# Jonah.net
KiCad netlist of a schematic drawn in EAGLE
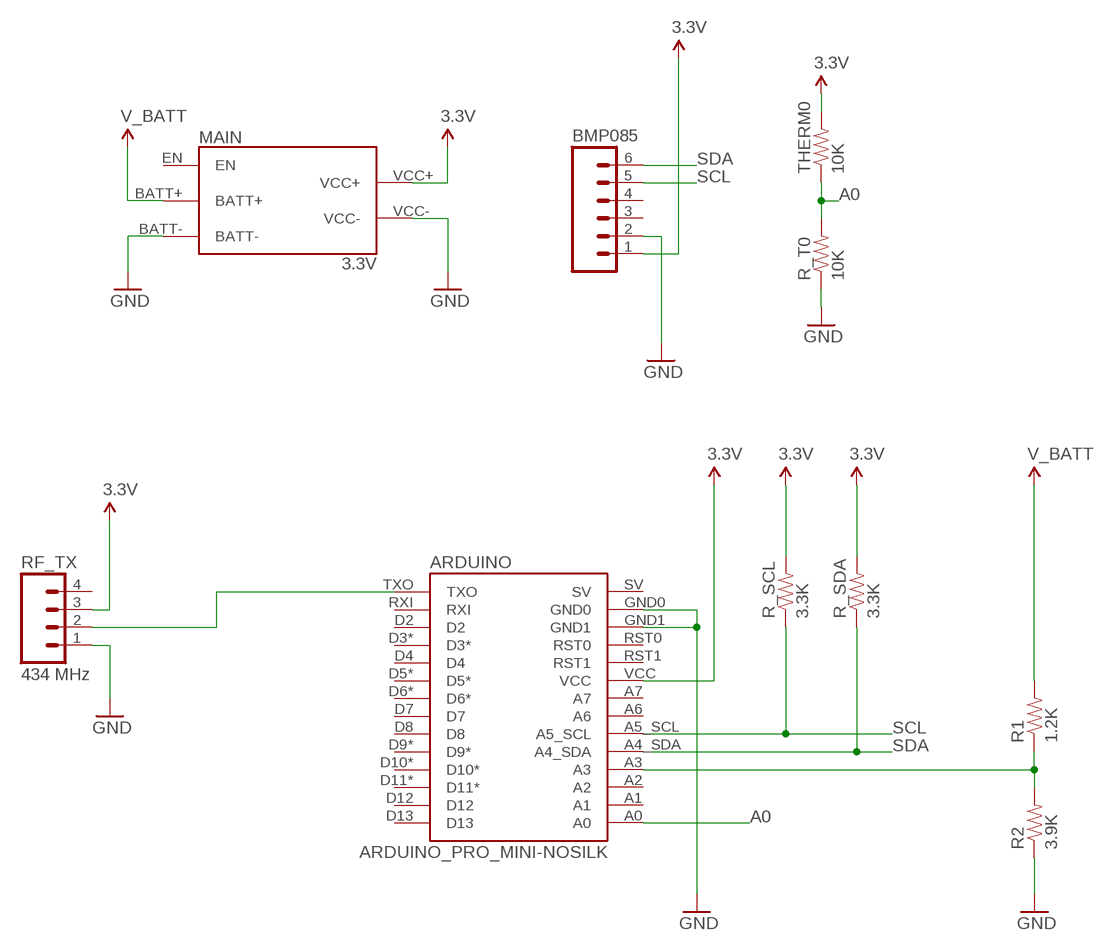
[diagram p0: schematic, sheet 1]

(export (version "E")
  (design (tool "Eeschema 10.0.6"))
  (components
    (comp (ref "ARDUINO")
      (value "ARDUINO_PRO_MINI-NOSILK")
      (footprint "eagle-import:ARDUINO_PRO_MINI-NOSILK")
      (libsource (lib "eagle-import") (part "ARDUINO_PRO_MINI-NOSILK"))
    )
    (comp (ref "BMP085")
      (value "M06SIP")
      (footprint "eagle-import:1X06")
      (libsource (lib "eagle-import") (part "M06SIP"))
    )
    (comp (ref "MAIN")
      (value "3.3V")
      (footprint "eagle-import:POWER-TPS6300X-NOSILK")
      (libsource (lib "eagle-import") (part "POWER-TPS6300X-NOSILK"))
    )
    (comp (ref "R1")
      (value "1.2K")
      (footprint "eagle-import:0805")
      (libsource (lib "eagle-import") (part "RESISTOR0805-RES"))
    )
    (comp (ref "R2")
      (value "3.9K")
      (footprint "eagle-import:0805")
      (libsource (lib "eagle-import") (part "RESISTOR0805-RES"))
    )
    (comp (ref "RF_TX")
      (value "434 MHz")
      (footprint "eagle-import:1X04")
      (libsource (lib "eagle-import") (part "M04PTH"))
    )
    (comp (ref "R_SCL")
      (value "3.3K")
      (footprint "eagle-import:0805")
      (libsource (lib "eagle-import") (part "RESISTOR0805-RES"))
    )
    (comp (ref "R_SDA")
      (value "3.3K")
      (footprint "eagle-import:0805")
      (libsource (lib "eagle-import") (part "RESISTOR0805-RES"))
    )
    (comp (ref "R_T0")
      (value "10K")
      (footprint "eagle-import:0805")
      (libsource (lib "eagle-import") (part "RESISTOR0805-RES"))
    )
    (comp (ref "THERM0")
      (value "10K")
      (footprint "eagle-import:0805")
      (libsource (lib "eagle-import") (part "RESISTOR0805-RES"))
    )
  )
  (nets
    (net (code "1") (name "/A0") (class "Default")
      (node (ref "ARDUINO") (pin "A0") (pinfunction "A0_A0") (pintype "bidirectional"))
      (node (ref "R_T0") (pin "2") (pinfunction "2_2") (pintype "passive"))
      (node (ref "THERM0") (pin "1") (pinfunction "1_1") (pintype "passive"))
    )
    (net (code "2") (name "/SCL") (class "Default")
      (node (ref "ARDUINO") (pin "A5_SCL") (pinfunction "A5_SCL_A5_SCL") (pintype "bidirectional"))
      (node (ref "BMP085") (pin "5") (pinfunction "5_5") (pintype "passive"))
      (node (ref "R_SCL") (pin "1") (pinfunction "1_1") (pintype "passive"))
    )
    (net (code "3") (name "/SDA") (class "Default")
      (node (ref "ARDUINO") (pin "A4_SDA") (pinfunction "A4_SDA_A4_SDA") (pintype "bidirectional"))
      (node (ref "BMP085") (pin "6") (pinfunction "6_6") (pintype "passive"))
      (node (ref "R_SDA") (pin "1") (pinfunction "1_1") (pintype "passive"))
    )
    (net (code "4") (name "3.3V") (class "Default")
      (node (ref "ARDUINO") (pin "VCC") (pinfunction "VCC_VCC") (pintype "bidirectional"))
      (node (ref "BMP085") (pin "1") (pinfunction "1_1") (pintype "passive"))
      (node (ref "MAIN") (pin "VCC+") (pinfunction "VCC+_VCC+") (pintype "bidirectional"))
      (node (ref "RF_TX") (pin "3") (pinfunction "3_3") (pintype "passive"))
      (node (ref "R_SCL") (pin "2") (pinfunction "2_2") (pintype "passive"))
      (node (ref "R_SDA") (pin "2") (pinfunction "2_2") (pintype "passive"))
      (node (ref "THERM0") (pin "2") (pinfunction "2_2") (pintype "passive"))
    )
    (net (code "5") (name "GND") (class "Default")
      (node (ref "ARDUINO") (pin "GND0") (pinfunction "GND0_GND0") (pintype "bidirectional"))
      (node (ref "ARDUINO") (pin "GND1") (pinfunction "GND1_GND1") (pintype "bidirectional"))
      (node (ref "BMP085") (pin "2") (pinfunction "2_2") (pintype "passive"))
      (node (ref "MAIN") (pin "BATT-") (pinfunction "BATT-_BATT-") (pintype "bidirectional"))
      (node (ref "MAIN") (pin "VCC-") (pinfunction "VCC-_VCC-") (pintype "bidirectional"))
      (node (ref "R2") (pin "1") (pinfunction "1_1") (pintype "passive"))
      (node (ref "RF_TX") (pin "1") (pinfunction "1_1") (pintype "passive"))
      (node (ref "R_T0") (pin "1") (pinfunction "1_1") (pintype "passive"))
    )
    (net (code "6") (name "Net-(ARDUINO-PadA3)") (class "Default")
      (node (ref "ARDUINO") (pin "A3") (pinfunction "A3_A3") (pintype "bidirectional"))
      (node (ref "R1") (pin "1") (pinfunction "1_1") (pintype "passive"))
      (node (ref "R2") (pin "2") (pinfunction "2_2") (pintype "passive"))
    )
    (net (code "7") (name "Net-(ARDUINO-PadTXO)") (class "Default")
      (node (ref "ARDUINO") (pin "TXO") (pinfunction "TXO_TXO") (pintype "bidirectional"))
      (node (ref "RF_TX") (pin "2") (pinfunction "2_2") (pintype "passive"))
    )
    (net (code "8") (name "V_BATT") (class "Default")
      (node (ref "MAIN") (pin "BATT+") (pinfunction "BATT+_BATT+") (pintype "bidirectional"))
      (node (ref "R1") (pin "2") (pinfunction "2_2") (pintype "passive"))
    )
    (net (code "9") (name "unconnected-(ARDUINO-PadA1)") (class "Default")
      (node (ref "ARDUINO") (pin "A1") (pinfunction "A1_A1") (pintype "bidirectional"))
    )
    (net (code "10") (name "unconnected-(ARDUINO-PadA2)") (class "Default")
      (node (ref "ARDUINO") (pin "A2") (pinfunction "A2_A2") (pintype "bidirectional"))
    )
    (net (code "11") (name "unconnected-(ARDUINO-PadA6)") (class "Default")
      (node (ref "ARDUINO") (pin "A6") (pinfunction "A6_A6") (pintype "bidirectional"))
    )
    (net (code "12") (name "unconnected-(ARDUINO-PadA7)") (class "Default")
      (node (ref "ARDUINO") (pin "A7") (pinfunction "A7_A7") (pintype "bidirectional"))
    )
    (net (code "13") (name "unconnected-(ARDUINO-PadD2)") (class "Default")
      (node (ref "ARDUINO") (pin "D2") (pinfunction "D2_D2") (pintype "bidirectional"))
    )
    (net (code "14") (name "unconnected-(ARDUINO-PadD3*)") (class "Default")
      (node (ref "ARDUINO") (pin "D3*") (pinfunction "D3*_D3*") (pintype "bidirectional"))
    )
    (net (code "15") (name "unconnected-(ARDUINO-PadD4)") (class "Default")
      (node (ref "ARDUINO") (pin "D4") (pinfunction "D4_D4") (pintype "bidirectional"))
    )
    (net (code "16") (name "unconnected-(ARDUINO-PadD5*)") (class "Default")
      (node (ref "ARDUINO") (pin "D5*") (pinfunction "D5*_D5*") (pintype "bidirectional"))
    )
    (net (code "17") (name "unconnected-(ARDUINO-PadD6*)") (class "Default")
      (node (ref "ARDUINO") (pin "D6*") (pinfunction "D6*_D6*") (pintype "bidirectional"))
    )
    (net (code "18") (name "unconnected-(ARDUINO-PadD7)") (class "Default")
      (node (ref "ARDUINO") (pin "D7") (pinfunction "D7_D7") (pintype "bidirectional"))
    )
    (net (code "19") (name "unconnected-(ARDUINO-PadD8)") (class "Default")
      (node (ref "ARDUINO") (pin "D8") (pinfunction "D8_D8") (pintype "bidirectional"))
    )
    (net (code "20") (name "unconnected-(ARDUINO-PadD9*)") (class "Default")
      (node (ref "ARDUINO") (pin "D9*") (pinfunction "D9*_D9*") (pintype "bidirectional"))
    )
    (net (code "21") (name "unconnected-(ARDUINO-PadD10*)") (class "Default")
      (node (ref "ARDUINO") (pin "D10*") (pinfunction "D10*_D10*") (pintype "bidirectional"))
    )
    (net (code "22") (name "unconnected-(ARDUINO-PadD11*)") (class "Default")
      (node (ref "ARDUINO") (pin "D11*") (pinfunction "D11*_D11*") (pintype "bidirectional"))
    )
    (net (code "23") (name "unconnected-(ARDUINO-PadD12)") (class "Default")
      (node (ref "ARDUINO") (pin "D12") (pinfunction "D12_D12") (pintype "bidirectional"))
    )
    (net (code "24") (name "unconnected-(ARDUINO-PadD13)") (class "Default")
      (node (ref "ARDUINO") (pin "D13") (pinfunction "D13_D13") (pintype "bidirectional"))
    )
    (net (code "25") (name "unconnected-(ARDUINO-PadRST0)") (class "Default")
      (node (ref "ARDUINO") (pin "RST0") (pinfunction "RST0_RST0") (pintype "bidirectional"))
    )
    (net (code "26") (name "unconnected-(ARDUINO-PadRST1)") (class "Default")
      (node (ref "ARDUINO") (pin "RST1") (pinfunction "RST1_RST1") (pintype "bidirectional"))
    )
    (net (code "27") (name "unconnected-(ARDUINO-PadRXI)") (class "Default")
      (node (ref "ARDUINO") (pin "RXI") (pinfunction "RXI_RXI") (pintype "bidirectional"))
    )
    (net (code "28") (name "unconnected-(ARDUINO-PadSV)") (class "Default")
      (node (ref "ARDUINO") (pin "SV") (pinfunction "SV_SV") (pintype "bidirectional"))
    )
    (net (code "29") (name "unconnected-(BMP085-Pad3)") (class "Default")
      (node (ref "BMP085") (pin "3") (pinfunction "3_3") (pintype "passive"))
    )
    (net (code "30") (name "unconnected-(BMP085-Pad4)") (class "Default")
      (node (ref "BMP085") (pin "4") (pinfunction "4_4") (pintype "passive"))
    )
    (net (code "31") (name "unconnected-(MAIN-PadEN)") (class "Default")
      (node (ref "MAIN") (pin "EN") (pinfunction "EN_EN") (pintype "bidirectional"))
    )
    (net (code "32") (name "unconnected-(RF_TX-Pad4)") (class "Default")
      (node (ref "RF_TX") (pin "4") (pinfunction "4_4") (pintype "passive"))
    )
  )
)
